# GPS.net
KiCad netlist of a schematic drawn in Altium Designer
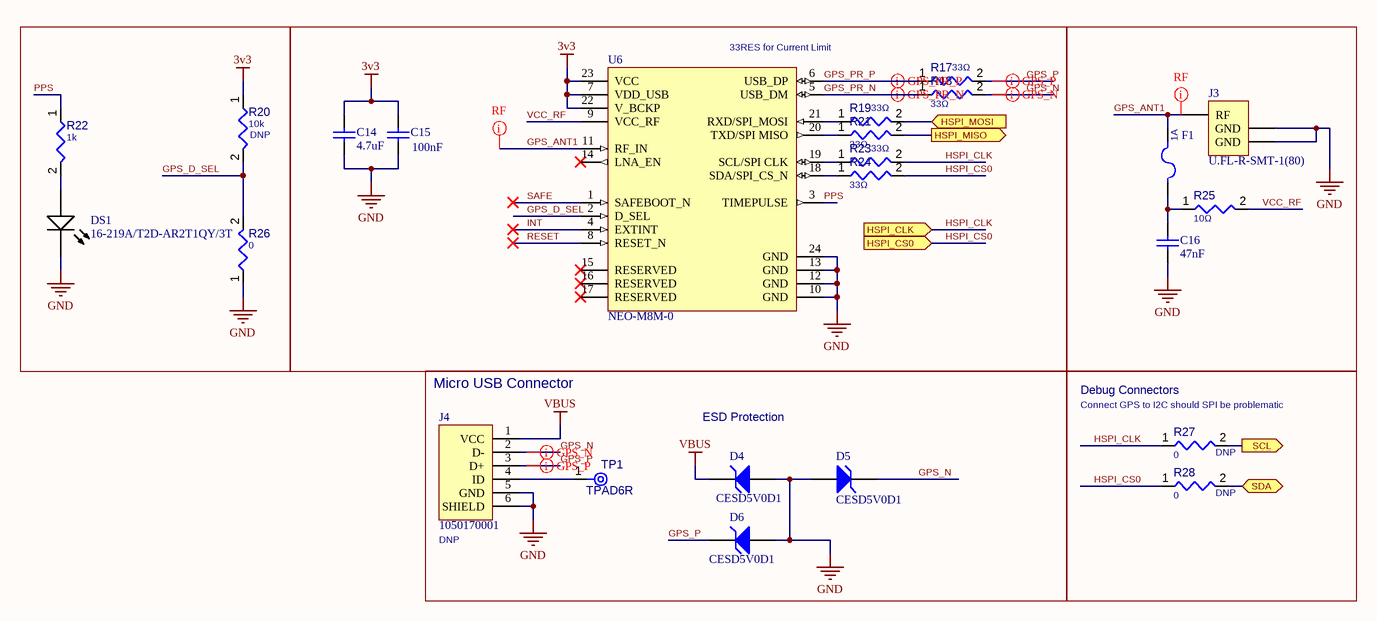
[diagram p0: GPS.SchDoc]

(export (version "E")
  (design (tool "Eeschema 10.0.6"))
  (components
    (comp (ref "C14")
      (value "GRM155R60J475ME87D")
      (footprint "Capacitor_0402")
      (description "6.3V 4.7uF X5R ±20% 0402 Multilayer Ceramic Capacitors MLCC - SMD/SMT ROHS")
      (fields (field (name "CAPACITANCE") "4.7uF") (field (name "TOLERANCE") "20%"))
      (libsource (lib "RIT Launch Initiative") (part "CAPACITOR"))
    )
    (comp (ref "C15")
      (value "GRM155R71E104KE14D")
      (footprint "Capacitor_0402")
      (description "Chip Capacitor 100nF 0402 25V X7R")
      (fields (field (name "CAPACITANCE") "100nF"))
      (libsource (lib "RIT Launch Initiative") (part "CAPACITOR"))
    )
    (comp (ref "C16")
      (value "GCM155R71H473KE02J")
      (footprint "Capacitor_0402")
      (description "Cap Ceramic 47nF 50V X7R 10% Pad SMD 0402 125C Automotive T/R")
      (fields (field (name "CAPACITANCE") "47nF"))
      (libsource (lib "RIT Launch Initiative") (part "CAPACITOR"))
    )
    (comp (ref "D4")
      (value "CESD5V0D1")
      (footprint "JSCJ-SOD-123-2_V")
      (description "Uni-driection ESD Protection Diode, 5 V, 1 uA, 2-Pin SOD-123, RoHS, Tape and Reel")
      (fields (field (name "MANUFACTURER") "Jiangsu Changjiang Electronics Technology"))
      (libsource (lib "RIT Launch Initiative") (part "DZEN-AK-2"))
    )
    (comp (ref "D5")
      (value "CESD5V0D1")
      (footprint "JSCJ-SOD-123-2_V")
      (description "Uni-driection ESD Protection Diode, 5 V, 1 uA, 2-Pin SOD-123, RoHS, Tape and Reel")
      (fields (field (name "MANUFACTURER") "Jiangsu Changjiang Electronics Technology"))
      (libsource (lib "RIT Launch Initiative") (part "DZEN-AK-2"))
    )
    (comp (ref "D6")
      (value "CESD5V0D1")
      (footprint "JSCJ-SOD-123-2_V")
      (description "Uni-driection ESD Protection Diode, 5 V, 1 uA, 2-Pin SOD-123, RoHS, Tape and Reel")
      (fields (field (name "MANUFACTURER") "Jiangsu Changjiang Electronics Technology"))
      (libsource (lib "RIT Launch Initiative") (part "DZEN-AK-2"))
    )
    (comp (ref "DS1")
      (value "16-219A/T2D-AR2T1QY/3T")
      (footprint "EVRL-0402-2_V")
      (description "Chip LED, White, 5 V, 10 mA, 30 mW, -40 to 85 degC, 2-Pin SMD (0402), RoHS, Tape and Reel")
      (fields (field (name "POWER") "30mW") (field (name "MANUFACTURER") "Everlight Electronics"))
      (libsource (lib "RIT Launch Initiative") (part "LED-WHITE-AK-2"))
    )
    (comp (ref "F1")
      (value "0466001.NRHF")
      (footprint "FP-0466-MFG")
      (description "Fuse Chip Very Fast Acting 1A 63V SMD Solder Pad 1206 T/R CSA")
      (libsource (lib "RIT Launch Initiative") (part "FUSE"))
    )
    (comp (ref "J3")
      (value "U.FL-R-SMT-1(80)")
      (footprint "FP-U_FL-R-SMT-1_80-MFG")
      (description "CONN U.FL RCPT STR 50 OHM SMD")
      (libsource (lib "RIT Launch Initiative") (part "U.FL-R-SMT-1(80)"))
    )
    (comp (ref "J4")
      (value "1050170001")
      (footprint "1050170001-Footprint-1")
      (description "Micro USB Connector; Data Recept.; Micro; B Type; Bottom Mount, SMT, with Solder Tabs, Lead-Free")
      (fields (field (name "DNP") "DNP"))
      (libsource (lib "RIT Launch Initiative") (part "1050170001"))
    )
    (comp (ref "R17")
      (value "33Ω")
      (footprint "RESC0402(1005)_L")
      (description "33R 0.063W 5% 0402 (1005 Metric)  SMD")
      (fields (field (name "TOLERANCE") "5%") (field (name "POWER") "63mW"))
      (libsource (lib "RIT Launch Initiative") (part "33R2J"))
    )
    (comp (ref "R18")
      (value "33Ω")
      (footprint "RESC0402(1005)_L")
      (description "33R 0.063W 5% 0402 (1005 Metric)  SMD")
      (fields (field (name "TOLERANCE") "5%") (field (name "POWER") "63mW"))
      (libsource (lib "RIT Launch Initiative") (part "33R2J"))
    )
    (comp (ref "R19")
      (value "33Ω")
      (footprint "RESC0402(1005)_L")
      (description "33R 0.063W 5% 0402 (1005 Metric)  SMD")
      (fields (field (name "TOLERANCE") "5%") (field (name "POWER") "63mW"))
      (libsource (lib "RIT Launch Initiative") (part "33R2J"))
    )
    (comp (ref "R20")
      (value "10k")
      (footprint "RESC0402(1005)_L")
      (description "Chip Resistor, 10 kOhms, +/-1 %, 63 mW, -55 to 125 degC, 0402")
      (fields (field (name "POWER") "63mW") (field (name "TOLERANCE") "1%") (field (name "DNP") "DNP"))
      (libsource (lib "RIT Launch Initiative") (part "RES-2"))
    )
    (comp (ref "R21")
      (value "33Ω")
      (footprint "RESC0402(1005)_L")
      (description "33R 0.063W 5% 0402 (1005 Metric)  SMD")
      (fields (field (name "TOLERANCE") "5%") (field (name "POWER") "63mW"))
      (libsource (lib "RIT Launch Initiative") (part "33R2J"))
    )
    (comp (ref "R22")
      (value "1k")
      (footprint "RESC0402(1005)_L")
      (description "Chip Resistor, 1 kOhms, +/-5 %, 63 mW, -55 to 155 degC, 0402")
      (fields (field (name "POWER") "63mW") (field (name "TOLERANCE") "5%"))
      (libsource (lib "RIT Launch Initiative") (part "RES-2"))
    )
    (comp (ref "R23")
      (value "33Ω")
      (footprint "RESC0402(1005)_L")
      (description "33R 0.063W 5% 0402 (1005 Metric)  SMD")
      (fields (field (name "TOLERANCE") "5%") (field (name "POWER") "63mW"))
      (libsource (lib "RIT Launch Initiative") (part "33R2J"))
    )
    (comp (ref "R24")
      (value "33Ω")
      (footprint "RESC0402(1005)_L")
      (description "33R 0.063W 5% 0402 (1005 Metric)  SMD")
      (fields (field (name "TOLERANCE") "5%") (field (name "POWER") "63mW"))
      (libsource (lib "RIT Launch Initiative") (part "33R2J"))
    )
    (comp (ref "R25")
      (value "10Ω")
      (footprint "RESC0402(1005)_L")
      (description "10R 0.063W 1% 0402 (1005 Metric)  SMD")
      (fields (field (name "POWER") "63mW") (field (name "TOLERANCE") "1%"))
      (libsource (lib "RIT Launch Initiative") (part "10R2F"))
    )
    (comp (ref "R26")
      (value "0")
      (footprint "RESC0402(1005)_L")
      (description "Jumper 0402")
      (libsource (lib "RIT Launch Initiative") (part "RES-2"))
    )
    (comp (ref "R27")
      (value "0")
      (footprint "RESC0402(1005)_L")
      (description "Jumper 0402")
      (fields (field (name "DNP") "DNP"))
      (libsource (lib "RIT Launch Initiative") (part "RES-2"))
    )
    (comp (ref "R28")
      (value "0")
      (footprint "RESC0402(1005)_L")
      (description "Jumper 0402")
      (fields (field (name "DNP") "DNP"))
      (libsource (lib "RIT Launch Initiative") (part "RES-2"))
    )
    (comp (ref "TP1")
      (value "TPAD6R")
      (footprint "TP06R")
      (description "0.6mm round")
      (libsource (lib "RIT Launch Initiative") (part "CMP-001-0001-4"))
    )
    (comp (ref "U6")
      (value "NEO-M8M-0")
      (footprint "NEO-M8M-0-Footprint-1")
      (description "GPS RF Receiver BeiDou, Galileo, GLONASS, GNSS, GPS 1.575GHz -167dBm")
      (libsource (lib "RIT Launch Initiative") (part "NEO-M8M-0-Symbol-1"))
    )
  )
  (nets
    (net (code "1") (name "/GPS_ANT1") (class "Default")
      (node (ref "F1") (pin "2") (pinfunction "2_2") (pintype "passive"))
      (node (ref "J3") (pin "1") (pinfunction "RF_1") (pintype "passive"))
      (node (ref "U6") (pin "11") (pinfunction "RF_IN_11") (pintype "input"))
    )
    (net (code "2") (name "/GPS_D_SEL") (class "Default")
      (node (ref "R20") (pin "2") (pinfunction "2_2") (pintype "passive"))
      (node (ref "R26") (pin "2") (pinfunction "2_2") (pintype "passive"))
      (node (ref "U6") (pin "2") (pinfunction "D_SEL_2") (pintype "input"))
    )
    (net (code "3") (name "/GPS_N") (class "Default")
      (node (ref "D5") (pin "2") (pinfunction "K_2") (pintype "passive"))
      (node (ref "J4") (pin "2") (pinfunction "D-_2") (pintype "passive"))
      (node (ref "R18") (pin "2") (pinfunction "2_2") (pintype "passive"))
    )
    (net (code "4") (name "/GPS_P") (class "Default")
      (node (ref "D6") (pin "2") (pinfunction "K_2") (pintype "passive"))
      (node (ref "J4") (pin "3") (pinfunction "D+_3") (pintype "passive"))
      (node (ref "R17") (pin "2") (pinfunction "2_2") (pintype "passive"))
    )
    (net (code "5") (name "/GPS_PR_N") (class "Default")
      (node (ref "R18") (pin "1") (pinfunction "1_1") (pintype "passive"))
      (node (ref "U6") (pin "5") (pinfunction "USB_DM_5") (pintype "bidirectional"))
    )
    (net (code "6") (name "/GPS_PR_P") (class "Default")
      (node (ref "R17") (pin "1") (pinfunction "1_1") (pintype "passive"))
      (node (ref "U6") (pin "6") (pinfunction "USB_DP_6") (pintype "bidirectional"))
    )
    (net (code "7") (name "/HSPI_CLK") (class "Default")
      (node (ref "R23") (pin "2") (pinfunction "2_2") (pintype "passive"))
      (node (ref "R27") (pin "1") (pinfunction "1_1") (pintype "passive"))
    )
    (net (code "8") (name "/HSPI_CS0") (class "Default")
      (node (ref "R24") (pin "2") (pinfunction "2_2") (pintype "passive"))
      (node (ref "R28") (pin "1") (pinfunction "1_1") (pintype "passive"))
    )
    (net (code "9") (name "/HSPI_MISO") (class "Default")
      (node (ref "R21") (pin "2") (pinfunction "2_2") (pintype "passive"))
    )
    (net (code "10") (name "/HSPI_MOSI") (class "Default")
      (node (ref "R19") (pin "2") (pinfunction "2_2") (pintype "passive"))
    )
    (net (code "11") (name "/INT") (class "Default")
      (node (ref "U6") (pin "4") (pinfunction "EXTINT_4") (pintype "input+no_connect"))
    )
    (net (code "12") (name "/PPS") (class "Default")
      (node (ref "R22") (pin "1") (pinfunction "1_1") (pintype "passive"))
      (node (ref "U6") (pin "3") (pinfunction "TIMEPULSE_3") (pintype "output"))
    )
    (net (code "13") (name "/RESET") (class "Default")
      (node (ref "U6") (pin "8") (pinfunction "RESET_N_8") (pintype "input+no_connect"))
    )
    (net (code "14") (name "/SAFE") (class "Default")
      (node (ref "U6") (pin "1") (pinfunction "SAFEBOOT_N_1") (pintype "input+no_connect"))
    )
    (net (code "15") (name "/SCL") (class "Default")
      (node (ref "R27") (pin "2") (pinfunction "2_2") (pintype "passive"))
    )
    (net (code "16") (name "/SDA") (class "Default")
      (node (ref "R28") (pin "2") (pinfunction "2_2") (pintype "passive"))
    )
    (net (code "17") (name "/VCC_RF") (class "Default")
      (node (ref "R25") (pin "2") (pinfunction "2_2") (pintype "passive"))
      (node (ref "U6") (pin "9") (pinfunction "VCC_RF_9") (pintype "power_in"))
    )
    (net (code "18") (name "3v3") (class "Default")
      (node (ref "C14") (pin "2") (pinfunction "2_2") (pintype "passive"))
      (node (ref "C15") (pin "2") (pinfunction "2_2") (pintype "passive"))
      (node (ref "R20") (pin "1") (pinfunction "1_1") (pintype "passive"))
      (node (ref "U6") (pin "22") (pinfunction "V_BCKP_22") (pintype "power_in"))
      (node (ref "U6") (pin "23") (pinfunction "VCC_23") (pintype "power_in"))
      (node (ref "U6") (pin "7") (pinfunction "VDD_USB_7") (pintype "power_in"))
    )
    (net (code "19") (name "GND") (class "Default")
      (node (ref "C14") (pin "1") (pinfunction "1_1") (pintype "passive"))
      (node (ref "C15") (pin "1") (pinfunction "1_1") (pintype "passive"))
      (node (ref "C16") (pin "1") (pinfunction "1_1") (pintype "passive"))
      (node (ref "D4") (pin "1") (pinfunction "A_1") (pintype "passive"))
      (node (ref "D5") (pin "1") (pinfunction "A_1") (pintype "passive"))
      (node (ref "D6") (pin "1") (pinfunction "A_1") (pintype "passive"))
      (node (ref "DS1") (pin "2") (pinfunction "K_2") (pintype "passive"))
      (node (ref "J3") (pin "2") (pinfunction "GND_2") (pintype "power_in"))
      (node (ref "J3") (pin "3") (pinfunction "GND_3") (pintype "power_in"))
      (node (ref "J4") (pin "5") (pinfunction "GND_5") (pintype "passive"))
      (node (ref "J4") (pin "6") (pinfunction "SHIELD_6") (pintype "passive"))
      (node (ref "R26") (pin "1") (pinfunction "1_1") (pintype "passive"))
      (node (ref "U6") (pin "10") (pinfunction "GND_10") (pintype "power_in"))
      (node (ref "U6") (pin "12") (pinfunction "GND_12") (pintype "power_in"))
      (node (ref "U6") (pin "13") (pinfunction "GND_13") (pintype "power_in"))
      (node (ref "U6") (pin "24") (pinfunction "GND_24") (pintype "power_in"))
    )
    (net (code "20") (name "Net-(C16-Pad2)") (class "Default")
      (node (ref "C16") (pin "2") (pinfunction "2_2") (pintype "passive"))
      (node (ref "F1") (pin "1") (pinfunction "1_1") (pintype "passive"))
      (node (ref "R25") (pin "1") (pinfunction "1_1") (pintype "passive"))
    )
    (net (code "21") (name "Net-(DS1-A)") (class "Default")
      (node (ref "DS1") (pin "1") (pinfunction "A_1") (pintype "passive"))
      (node (ref "R22") (pin "2") (pinfunction "2_2") (pintype "passive"))
    )
    (net (code "22") (name "Net-(J4-ID)") (class "Default")
      (node (ref "J4") (pin "4") (pinfunction "ID_4") (pintype "passive"))
      (node (ref "TP1") (pin "1") (pinfunction "TP_1") (pintype "passive"))
    )
    (net (code "23") (name "Net-(U6-RXD{slash}SPI_MOSI)") (class "Default")
      (node (ref "R19") (pin "1") (pinfunction "1_1") (pintype "passive"))
      (node (ref "U6") (pin "21") (pinfunction "RXD/SPI_MOSI_21") (pintype "input"))
    )
    (net (code "24") (name "Net-(U6-SCL{slash}SPI_CLK)") (class "Default")
      (node (ref "R23") (pin "1") (pinfunction "1_1") (pintype "passive"))
      (node (ref "U6") (pin "19") (pinfunction "SCL/SPI_CLK_19") (pintype "bidirectional"))
    )
    (net (code "25") (name "Net-(U6-SDA{slash}SPI_CS_N)") (class "Default")
      (node (ref "R24") (pin "1") (pinfunction "1_1") (pintype "passive"))
      (node (ref "U6") (pin "18") (pinfunction "SDA/SPI_CS_N_18") (pintype "bidirectional"))
    )
    (net (code "26") (name "Net-(U6-TXD{slash}SPI_MISO)") (class "Default")
      (node (ref "R21") (pin "1") (pinfunction "1_1") (pintype "passive"))
      (node (ref "U6") (pin "20") (pinfunction "TXD/SPI_MISO_20") (pintype "output"))
    )
    (net (code "27") (name "VBUS") (class "Default")
      (node (ref "D4") (pin "2") (pinfunction "K_2") (pintype "passive"))
      (node (ref "J4") (pin "1") (pinfunction "VCC_1") (pintype "passive"))
    )
    (net (code "28") (name "unconnected-(U6-LNA_EN-Pad14)") (class "Default")
      (node (ref "U6") (pin "14") (pinfunction "LNA_EN_14") (pintype "output+no_connect"))
    )
    (net (code "29") (name "unconnected-(U6-RESERVED-Pad15)") (class "Default")
      (node (ref "U6") (pin "15") (pinfunction "RESERVED_15") (pintype "passive+no_connect"))
    )
    (net (code "30") (name "unconnected-(U6-RESERVED-Pad16)") (class "Default")
      (node (ref "U6") (pin "16") (pinfunction "RESERVED_16") (pintype "passive+no_connect"))
    )
    (net (code "31") (name "unconnected-(U6-RESERVED-Pad17)") (class "Default")
      (node (ref "U6") (pin "17") (pinfunction "RESERVED_17") (pintype "passive+no_connect"))
    )
  )
)
